# USB_Connector.net
KiCad netlist of a schematic drawn in Altium Designer
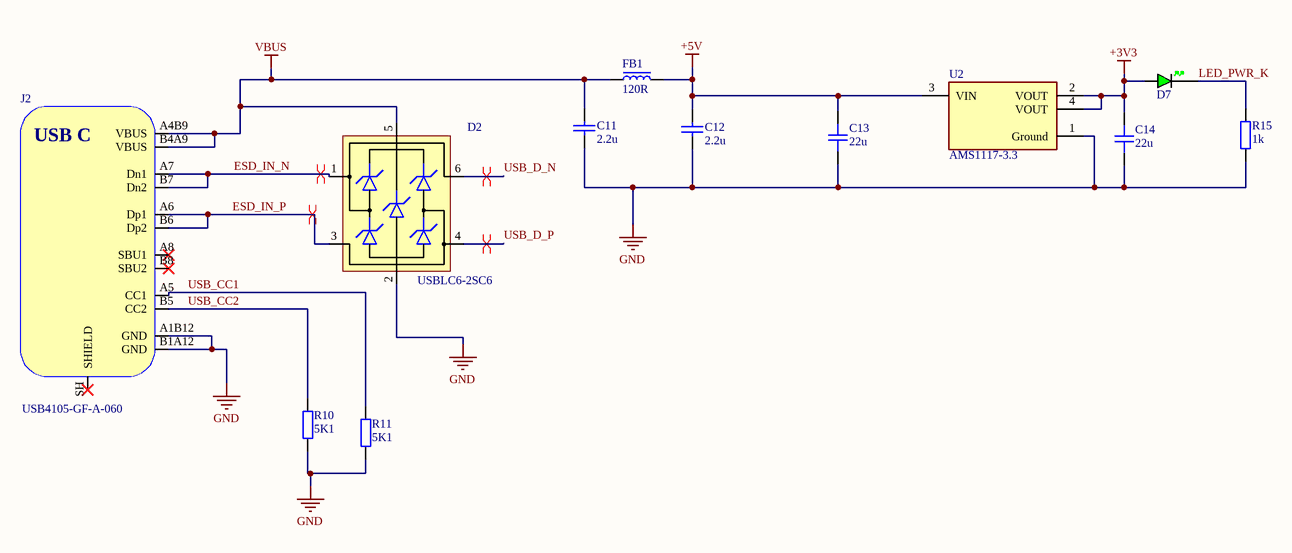
[diagram p0: USB_Connector.SchDoc]

(export (version "E")
  (design (tool "Eeschema 10.0.6"))
  (components
    (comp (ref "C11")
      (value "2.2u")
      (footprint "CAPC1608X90X35NL15T15")
      (fields (field (name "MANUFACTURER") "Kemet") (field (name "PART NUMBER") "C0603C225M4PACTU"))
      (libsource (lib "Altium Content Vault") (part "CAP"))
    )
    (comp (ref "C12")
      (value "2.2u")
      (footprint "CAPC1608X90X35NL15T15")
      (fields (field (name "MANUFACTURER") "Kemet") (field (name "PART NUMBER") "C0603C225M4PACTU"))
      (libsource (lib "Altium Content Vault") (part "CAP"))
    )
    (comp (ref "C13")
      (value "22u")
      (footprint "CAP_0805")
      (description "Capacitor SMD 0805")
      (libsource (lib "Schematic-Lib-PhilsLab") (part "CAP_0805"))
    )
    (comp (ref "C14")
      (value "22u")
      (footprint "CAP_0805")
      (description "Capacitor SMD 0805")
      (libsource (lib "Schematic-Lib-PhilsLab") (part "CAP_0805"))
    )
    (comp (ref "D2")
      (value "USBLC6-2SC6")
      (footprint "SOT-23-6")
      (description "Low-Capacitance ESD Protection USB")
      (fields (field (name "MANUFACTURER") "STMicroelectronics"))
      (libsource (lib "Schematic-Lib-PhilsLab") (part "USBLC6-2SC6"))
    )
    (comp (ref "D7")
      (value "GREEN")
      (footprint "LED_0402_GREEN")
      (description "LED 0402 GREEN SMD")
      (libsource (lib "Schematic-Lib-PhilsLab") (part "LED_0402_GREEN"))
    )
    (comp (ref "FB1")
      (value "120R")
      (footprint "FB_0603")
      (description "Ferrite Bead SMD 0603")
      (libsource (lib "Schematic-Lib-PhilsLab") (part "FB_0603"))
    )
    (comp (ref "J2")
      (value "USB4105-GF-A-060")
      (footprint "USB4105-GF-A-060")
      (description "USB Connector Type C SMT 12 Pin")
      (fields (field (name "MANUFACTURER") "GCT"))
      (libsource (lib "Schematic-Lib-PhilsLab") (part "USB4105-GF-A-060"))
    )
    (comp (ref "R10")
      (value "5K1")
      (footprint "RES_0402")
      (description "Resistor SMD 0402")
      (libsource (lib "Schematic-Lib-PhilsLab") (part "RES_0402"))
    )
    (comp (ref "R11")
      (value "5K1")
      (footprint "RES_0402")
      (description "Resistor SMD 0402")
      (libsource (lib "Schematic-Lib-PhilsLab") (part "RES_0402"))
    )
    (comp (ref "R15")
      (value "1k")
      (footprint "RES_0402")
      (description "Resistor SMD 0402")
      (libsource (lib "Schematic-Lib-PhilsLab") (part "RES_0402"))
    )
    (comp (ref "U2")
      (value "AMS1117-3.3")
      (footprint "FP-AMS1117-IPC_C")
      (description "LDO Voltage Regulators 1A, 3.3V")
      (fields
        (field (name "OCTOPART") "https://octopart.com/ams1117-3.3-advanced+monolithic+systems-25899300")
        (field (name "MANUFACTURER") "Advanced Monolithic Systems")
      )
      (libsource (lib "Altium Content Vault") (part "8bdbb5f8e77002000e30dd2845d0354"))
    )
  )
  (nets
    (net (code "1") (name "+3V3") (class "Default")
      (node (ref "C14") (pin "2") (pinfunction "2_2") (pintype "passive"))
      (node (ref "D7") (pin "A") (pinfunction "A_A") (pintype "passive"))
      (node (ref "U2") (pin "2") (pinfunction "VOUT_2") (pintype "passive"))
      (node (ref "U2") (pin "4") (pinfunction "VOUT_4") (pintype "passive"))
    )
    (net (code "2") (name "+5V") (class "Default")
      (node (ref "C12") (pin "2") (pinfunction "2_2") (pintype "passive"))
      (node (ref "C13") (pin "2") (pinfunction "2_2") (pintype "passive"))
      (node (ref "FB1") (pin "2") (pinfunction "2_2") (pintype "passive"))
      (node (ref "U2") (pin "3") (pinfunction "VIN_3") (pintype "power_in"))
    )
    (net (code "3") (name "/ESD_IN_N") (class "Default")
      (node (ref "D2") (pin "1") (pinfunction "IO1_1") (pintype "bidirectional"))
      (node (ref "J2") (pin "A7") (pinfunction "Dn1_A7") (pintype "passive"))
      (node (ref "J2") (pin "B7") (pinfunction "Dn2_B7") (pintype "passive"))
    )
    (net (code "4") (name "/ESD_IN_P") (class "Default")
      (node (ref "D2") (pin "3") (pinfunction "IO2_3") (pintype "bidirectional"))
      (node (ref "J2") (pin "A6") (pinfunction "Dp1_A6") (pintype "passive"))
      (node (ref "J2") (pin "B6") (pinfunction "Dp2_B6") (pintype "passive"))
    )
    (net (code "5") (name "/LED_PWR_K") (class "Default")
      (node (ref "D7") (pin "K") (pinfunction "K_K") (pintype "passive"))
      (node (ref "R15") (pin "2") (pinfunction "2_2") (pintype "passive"))
    )
    (net (code "6") (name "/USB_CC1") (class "Default")
      (node (ref "J2") (pin "A5") (pinfunction "CC1_A5") (pintype "passive"))
      (node (ref "R11") (pin "2") (pinfunction "2_2") (pintype "passive"))
    )
    (net (code "7") (name "/USB_CC2") (class "Default")
      (node (ref "J2") (pin "B5") (pinfunction "CC2_B5") (pintype "passive"))
      (node (ref "R10") (pin "2") (pinfunction "2_2") (pintype "passive"))
    )
    (net (code "8") (name "/USB_D_N") (class "Default")
      (node (ref "D2") (pin "6") (pinfunction "IO1_6") (pintype "bidirectional"))
    )
    (net (code "9") (name "/USB_D_P") (class "Default")
      (node (ref "D2") (pin "4") (pinfunction "IO2_4") (pintype "bidirectional"))
    )
    (net (code "10") (name "GND") (class "Default")
      (node (ref "C11") (pin "1") (pinfunction "1_1") (pintype "passive"))
      (node (ref "C12") (pin "1") (pinfunction "1_1") (pintype "passive"))
      (node (ref "C13") (pin "1") (pinfunction "1_1") (pintype "passive"))
      (node (ref "C14") (pin "1") (pinfunction "1_1") (pintype "passive"))
      (node (ref "D2") (pin "2") (pinfunction "GND_2") (pintype "power_in"))
      (node (ref "J2") (pin "A1B12") (pinfunction "GND_A1B12") (pintype "passive"))
      (node (ref "J2") (pin "B1A12") (pinfunction "GND_B1A12") (pintype "passive"))
      (node (ref "R10") (pin "1") (pinfunction "1_1") (pintype "passive"))
      (node (ref "R11") (pin "1") (pinfunction "1_1") (pintype "passive"))
      (node (ref "R15") (pin "1") (pinfunction "1_1") (pintype "passive"))
      (node (ref "U2") (pin "1") (pinfunction "Ground_1") (pintype "power_in"))
    )
    (net (code "11") (name "VBUS") (class "Default")
      (node (ref "C11") (pin "2") (pinfunction "2_2") (pintype "passive"))
      (node (ref "D2") (pin "5") (pinfunction "VBUS_5") (pintype "power_in"))
      (node (ref "FB1") (pin "1") (pinfunction "1_1") (pintype "passive"))
      (node (ref "J2") (pin "A4B9") (pinfunction "VBUS_A4B9") (pintype "passive"))
      (node (ref "J2") (pin "B4A9") (pinfunction "VBUS_B4A9") (pintype "passive"))
    )
    (net (code "12") (name "unconnected-(J2-SBU1-PadA8)") (class "Default")
      (node (ref "J2") (pin "A8") (pinfunction "SBU1_A8") (pintype "passive+no_connect"))
    )
    (net (code "13") (name "unconnected-(J2-SBU2-PadB8)") (class "Default")
      (node (ref "J2") (pin "B8") (pinfunction "SBU2_B8") (pintype "passive+no_connect"))
    )
    (net (code "14") (name "unconnected-(J2-SHIELD-PadSH)") (class "Default")
      (node (ref "J2") (pin "SH") (pinfunction "SHIELD_SH") (pintype "passive+no_connect"))
    )
  )
)
